# Display_Module.net
KiCad netlist of a schematic drawn in Altium Designer
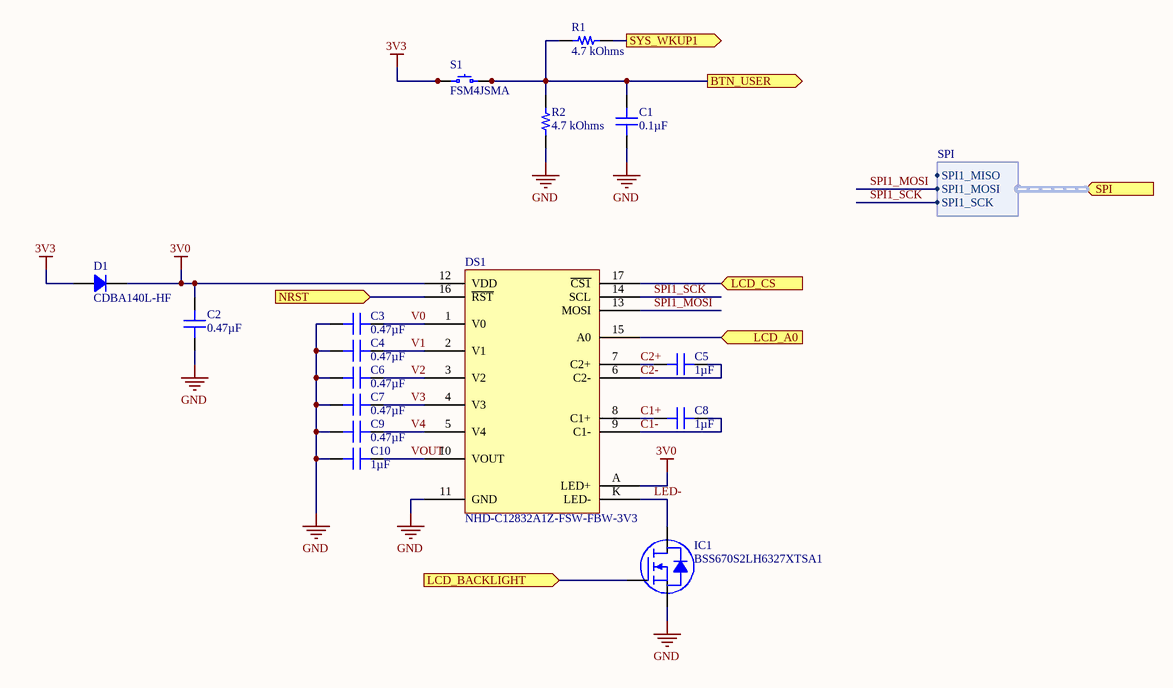
[diagram p0: Display Module.SchDoc]

(export (version "E")
  (design (tool "Eeschema 10.0.6"))
  (components
    (comp (ref "C1")
      (value "0.1µF")
      (footprint "CAP 0603_1608")
      (description "CAP CER 0.1UF 50V X7R 0603")
      (fields (field (name "PART NUMBER") "06035C104JAT4A") (field (name "MANUFACTURER") "AVX Corporation"))
      (libsource (lib "altiumlibrary.com") (part "Capacitor"))
    )
    (comp (ref "C2")
      (value "0.47µF")
      (footprint "CAP 0603_1608")
      (description "CAP CER 0.47UF 10V X7R 0603")
      (fields
        (field (name "PART NUMBER") "0603B474K100CT")
        (field (name "MANUFACTURER") "Walsin Technology Corporation")
      )
      (libsource (lib "altiumlibrary.com") (part "Capacitor"))
    )
    (comp (ref "C3")
      (value "0.47µF")
      (footprint "CAP 0603_1608")
      (description "CAP CER 0.47UF 10V X7R 0603")
      (fields
        (field (name "PART NUMBER") "0603B474K100CT")
        (field (name "MANUFACTURER") "Walsin Technology Corporation")
      )
      (libsource (lib "altiumlibrary.com") (part "Capacitor"))
    )
    (comp (ref "C4")
      (value "0.47µF")
      (footprint "CAP 0603_1608")
      (description "CAP CER 0.47UF 10V X7R 0603")
      (fields
        (field (name "PART NUMBER") "0603B474K100CT")
        (field (name "MANUFACTURER") "Walsin Technology Corporation")
      )
      (libsource (lib "altiumlibrary.com") (part "Capacitor"))
    )
    (comp (ref "C5")
      (value "1µF")
      (footprint "CAP 0603_1608")
      (description "CAP CER 1UF 10V X7R 0603")
      (fields (field (name "PART NUMBER") "LMK107B7105KA-T") (field (name "MANUFACTURER") "Taiyo Yuden"))
      (libsource (lib "altiumlibrary.com") (part "Capacitor"))
    )
    (comp (ref "C6")
      (value "0.47µF")
      (footprint "CAP 0603_1608")
      (description "CAP CER 0.47UF 10V X7R 0603")
      (fields
        (field (name "PART NUMBER") "0603B474K100CT")
        (field (name "MANUFACTURER") "Walsin Technology Corporation")
      )
      (libsource (lib "altiumlibrary.com") (part "Capacitor"))
    )
    (comp (ref "C7")
      (value "0.47µF")
      (footprint "CAP 0603_1608")
      (description "CAP CER 0.47UF 10V X7R 0603")
      (fields
        (field (name "PART NUMBER") "0603B474K100CT")
        (field (name "MANUFACTURER") "Walsin Technology Corporation")
      )
      (libsource (lib "altiumlibrary.com") (part "Capacitor"))
    )
    (comp (ref "C8")
      (value "1µF")
      (footprint "CAP 0603_1608")
      (description "CAP CER 1UF 10V X7R 0603")
      (fields (field (name "PART NUMBER") "LMK107B7105KA-T") (field (name "MANUFACTURER") "Taiyo Yuden"))
      (libsource (lib "altiumlibrary.com") (part "Capacitor"))
    )
    (comp (ref "C9")
      (value "0.47µF")
      (footprint "CAP 0603_1608")
      (description "CAP CER 0.47UF 10V X7R 0603")
      (fields
        (field (name "PART NUMBER") "0603B474K100CT")
        (field (name "MANUFACTURER") "Walsin Technology Corporation")
      )
      (libsource (lib "altiumlibrary.com") (part "Capacitor"))
    )
    (comp (ref "C10")
      (value "1µF")
      (footprint "CAP 0603_1608")
      (description "CAP CER 1UF 10V X7R 0603")
      (fields (field (name "PART NUMBER") "LMK107B7105KA-T") (field (name "MANUFACTURER") "Taiyo Yuden"))
      (libsource (lib "altiumlibrary.com") (part "Capacitor"))
    )
    (comp (ref "D1")
      (value "CDBA140L-HF")
      (footprint "DO214AC SMA")
      (description "DIODE SCHOTTKY 40V 1A DO214AC")
      (fields (field (name "MANUFACTURER") "Comchip Technology"))
      (libsource (lib "altiumlibrary.com") (part "Diode"))
    )
    (comp (ref "DS1")
      (value "NHD-C12832A1Z-FSW-FBW-3V3")
      (footprint "NHD-C12832A1Z WHITE")
      (description "LCD COG GRAPHIC 128X32")
      (fields (field (name "MANUFACTURER") "Newhaven Display Intl"))
      (libsource (lib "altiumlibrary.com") (part "Newhaven NHD-C12832A1Z"))
    )
    (comp (ref "IC1")
      (value "BSS670S2LH6327XTSA1")
      (footprint "INFINEON SOT-23-3")
      (description "MOSFET N-CH 55V 540MA SOT23")
      (fields (field (name "MANUFACTURER") "Infineon Technologies"))
      (libsource (lib "altiumlibrary.com") (part "INFINEON MOSFET N-CH SOT-23-3 GSD"))
    )
    (comp (ref "R1")
      (value "4.7 kOhms")
      (footprint "RES 0603_1608")
      (description "RES SMD 4.7K OHM 1% 1/10W 0603")
      (fields
        (field (name "PART NUMBER") "ERJ-3EKF4701V")
        (field (name "MANUFACTURER") "Panasonic Electronic Components")
      )
      (libsource (lib "altiumlibrary.com") (part "Resistor"))
    )
    (comp (ref "R2")
      (value "4.7 kOhms")
      (footprint "RES 0603_1608")
      (description "RES SMD 4.7K OHM 1% 1/10W 0603")
      (fields
        (field (name "PART NUMBER") "ERJ-3EKF4701V")
        (field (name "MANUFACTURER") "Panasonic Electronic Components")
      )
      (libsource (lib "altiumlibrary.com") (part "Resistor"))
    )
    (comp (ref "S1")
      (value "FSM4JSMA")
      (footprint "TE FSM4JSMA")
      (description "SWITCH TACTILE SPST-NO 0.05A 24V")
      (fields (field (name "MANUFACTURER") "TE Connectivity ALCOSWITCH Switches"))
      (libsource (lib "altiumlibrary.com") (part "SPST-NO 4 PIN"))
    )
  )
  (nets
    (net (code "2") (name "/BTN_USER") (class "Default")
      (node (ref "C1") (pin "2") (pinfunction "2_2") (pintype "passive"))
      (node (ref "R1") (pin "2") (pinfunction "2_2") (pintype "passive"))
      (node (ref "R2") (pin "2") (pinfunction "2_2") (pintype "passive"))
      (node (ref "S1") (pin "3") (pinfunction "3_3") (pintype "passive"))
      (node (ref "S1") (pin "4") (pinfunction "4_4") (pintype "passive"))
    )
    (net (code "3") (name "/C1+") (class "Default")
      (node (ref "C8") (pin "1") (pinfunction "1_1") (pintype "passive"))
      (node (ref "DS1") (pin "8") (pinfunction "C1+_8") (pintype "passive"))
    )
    (net (code "4") (name "/C1-") (class "Default")
      (node (ref "C8") (pin "2") (pinfunction "2_2") (pintype "passive"))
      (node (ref "DS1") (pin "9") (pinfunction "C1-_9") (pintype "passive"))
    )
    (net (code "5") (name "/C2+") (class "Default")
      (node (ref "C5") (pin "1") (pinfunction "1_1") (pintype "passive"))
      (node (ref "DS1") (pin "7") (pinfunction "C2+_7") (pintype "passive"))
    )
    (net (code "6") (name "/C2-") (class "Default")
      (node (ref "C5") (pin "2") (pinfunction "2_2") (pintype "passive"))
      (node (ref "DS1") (pin "6") (pinfunction "C2-_6") (pintype "passive"))
    )
    (net (code "7") (name "/LCD_A0") (class "Default")
      (node (ref "DS1") (pin "15") (pinfunction "A0_15") (pintype "passive"))
    )
    (net (code "8") (name "/LCD_BACKLIGHT") (class "Default")
      (node (ref "IC1") (pin "1") (pinfunction "G_1") (pintype "passive"))
    )
    (net (code "9") (name "/LCD_CS") (class "Default")
      (node (ref "DS1") (pin "17") (pinfunction "~{CS1}_17") (pintype "passive"))
    )
    (net (code "10") (name "/LED-") (class "Default")
      (node (ref "DS1") (pin "K") (pinfunction "LED-_K") (pintype "passive"))
      (node (ref "IC1") (pin "3") (pinfunction "D_3") (pintype "passive"))
    )
    (net (code "11") (name "/NRST") (class "Default")
      (node (ref "DS1") (pin "16") (pinfunction "~{RST}_16") (pintype "passive"))
    )
    (net (code "12") (name "/SPI1_MOSI") (class "Default")
      (node (ref "DS1") (pin "13") (pinfunction "MOSI_13") (pintype "passive"))
    )
    (net (code "13") (name "/SPI1_SCK") (class "Default")
      (node (ref "DS1") (pin "14") (pinfunction "SCL_14") (pintype "passive"))
    )
    (net (code "14") (name "/SYS_WKUP1") (class "Default")
      (node (ref "R1") (pin "1") (pinfunction "1_1") (pintype "passive"))
    )
    (net (code "15") (name "/V0") (class "Default")
      (node (ref "C3") (pin "1") (pinfunction "1_1") (pintype "passive"))
      (node (ref "DS1") (pin "1") (pinfunction "V0_1") (pintype "passive"))
    )
    (net (code "16") (name "/V1") (class "Default")
      (node (ref "C4") (pin "1") (pinfunction "1_1") (pintype "passive"))
      (node (ref "DS1") (pin "2") (pinfunction "V1_2") (pintype "passive"))
    )
    (net (code "17") (name "/V2") (class "Default")
      (node (ref "C6") (pin "1") (pinfunction "1_1") (pintype "passive"))
      (node (ref "DS1") (pin "3") (pinfunction "V2_3") (pintype "passive"))
    )
    (net (code "18") (name "/V3") (class "Default")
      (node (ref "C7") (pin "1") (pinfunction "1_1") (pintype "passive"))
      (node (ref "DS1") (pin "4") (pinfunction "V3_4") (pintype "passive"))
    )
    (net (code "19") (name "/V4") (class "Default")
      (node (ref "C9") (pin "1") (pinfunction "1_1") (pintype "passive"))
      (node (ref "DS1") (pin "5") (pinfunction "V4_5") (pintype "passive"))
    )
    (net (code "20") (name "/VOUT") (class "Default")
      (node (ref "C10") (pin "2") (pinfunction "2_2") (pintype "passive"))
      (node (ref "DS1") (pin "10") (pinfunction "VOUT_10") (pintype "passive"))
    )
    (net (code "22") (name "3V0") (class "Default")
      (node (ref "C2") (pin "1") (pinfunction "1_1") (pintype "passive"))
      (node (ref "D1") (pin "2") (pinfunction "2_2") (pintype "passive"))
      (node (ref "DS1") (pin "12") (pinfunction "VDD_12") (pintype "passive"))
      (node (ref "DS1") (pin "A") (pinfunction "LED+_A") (pintype "passive"))
    )
    (net (code "23") (name "3V3") (class "Default")
      (node (ref "D1") (pin "1") (pinfunction "1_1") (pintype "passive"))
      (node (ref "S1") (pin "1") (pinfunction "1_1") (pintype "passive"))
      (node (ref "S1") (pin "2") (pinfunction "2_2") (pintype "passive"))
    )
    (net (code "24") (name "GND") (class "Default")
      (node (ref "C1") (pin "1") (pinfunction "1_1") (pintype "passive"))
      (node (ref "C10") (pin "1") (pinfunction "1_1") (pintype "passive"))
      (node (ref "C2") (pin "2") (pinfunction "2_2") (pintype "passive"))
      (node (ref "C3") (pin "2") (pinfunction "2_2") (pintype "passive"))
      (node (ref "C4") (pin "2") (pinfunction "2_2") (pintype "passive"))
      (node (ref "C6") (pin "2") (pinfunction "2_2") (pintype "passive"))
      (node (ref "C7") (pin "2") (pinfunction "2_2") (pintype "passive"))
      (node (ref "C9") (pin "2") (pinfunction "2_2") (pintype "passive"))
      (node (ref "DS1") (pin "11") (pinfunction "GND_11") (pintype "passive"))
      (node (ref "IC1") (pin "2") (pinfunction "S_2") (pintype "passive"))
      (node (ref "R2") (pin "1") (pinfunction "1_1") (pintype "passive"))
    )
  )
)
